# CD_CONTROL_BRD.net
KiCad netlist of a schematic drawn in EAGLE
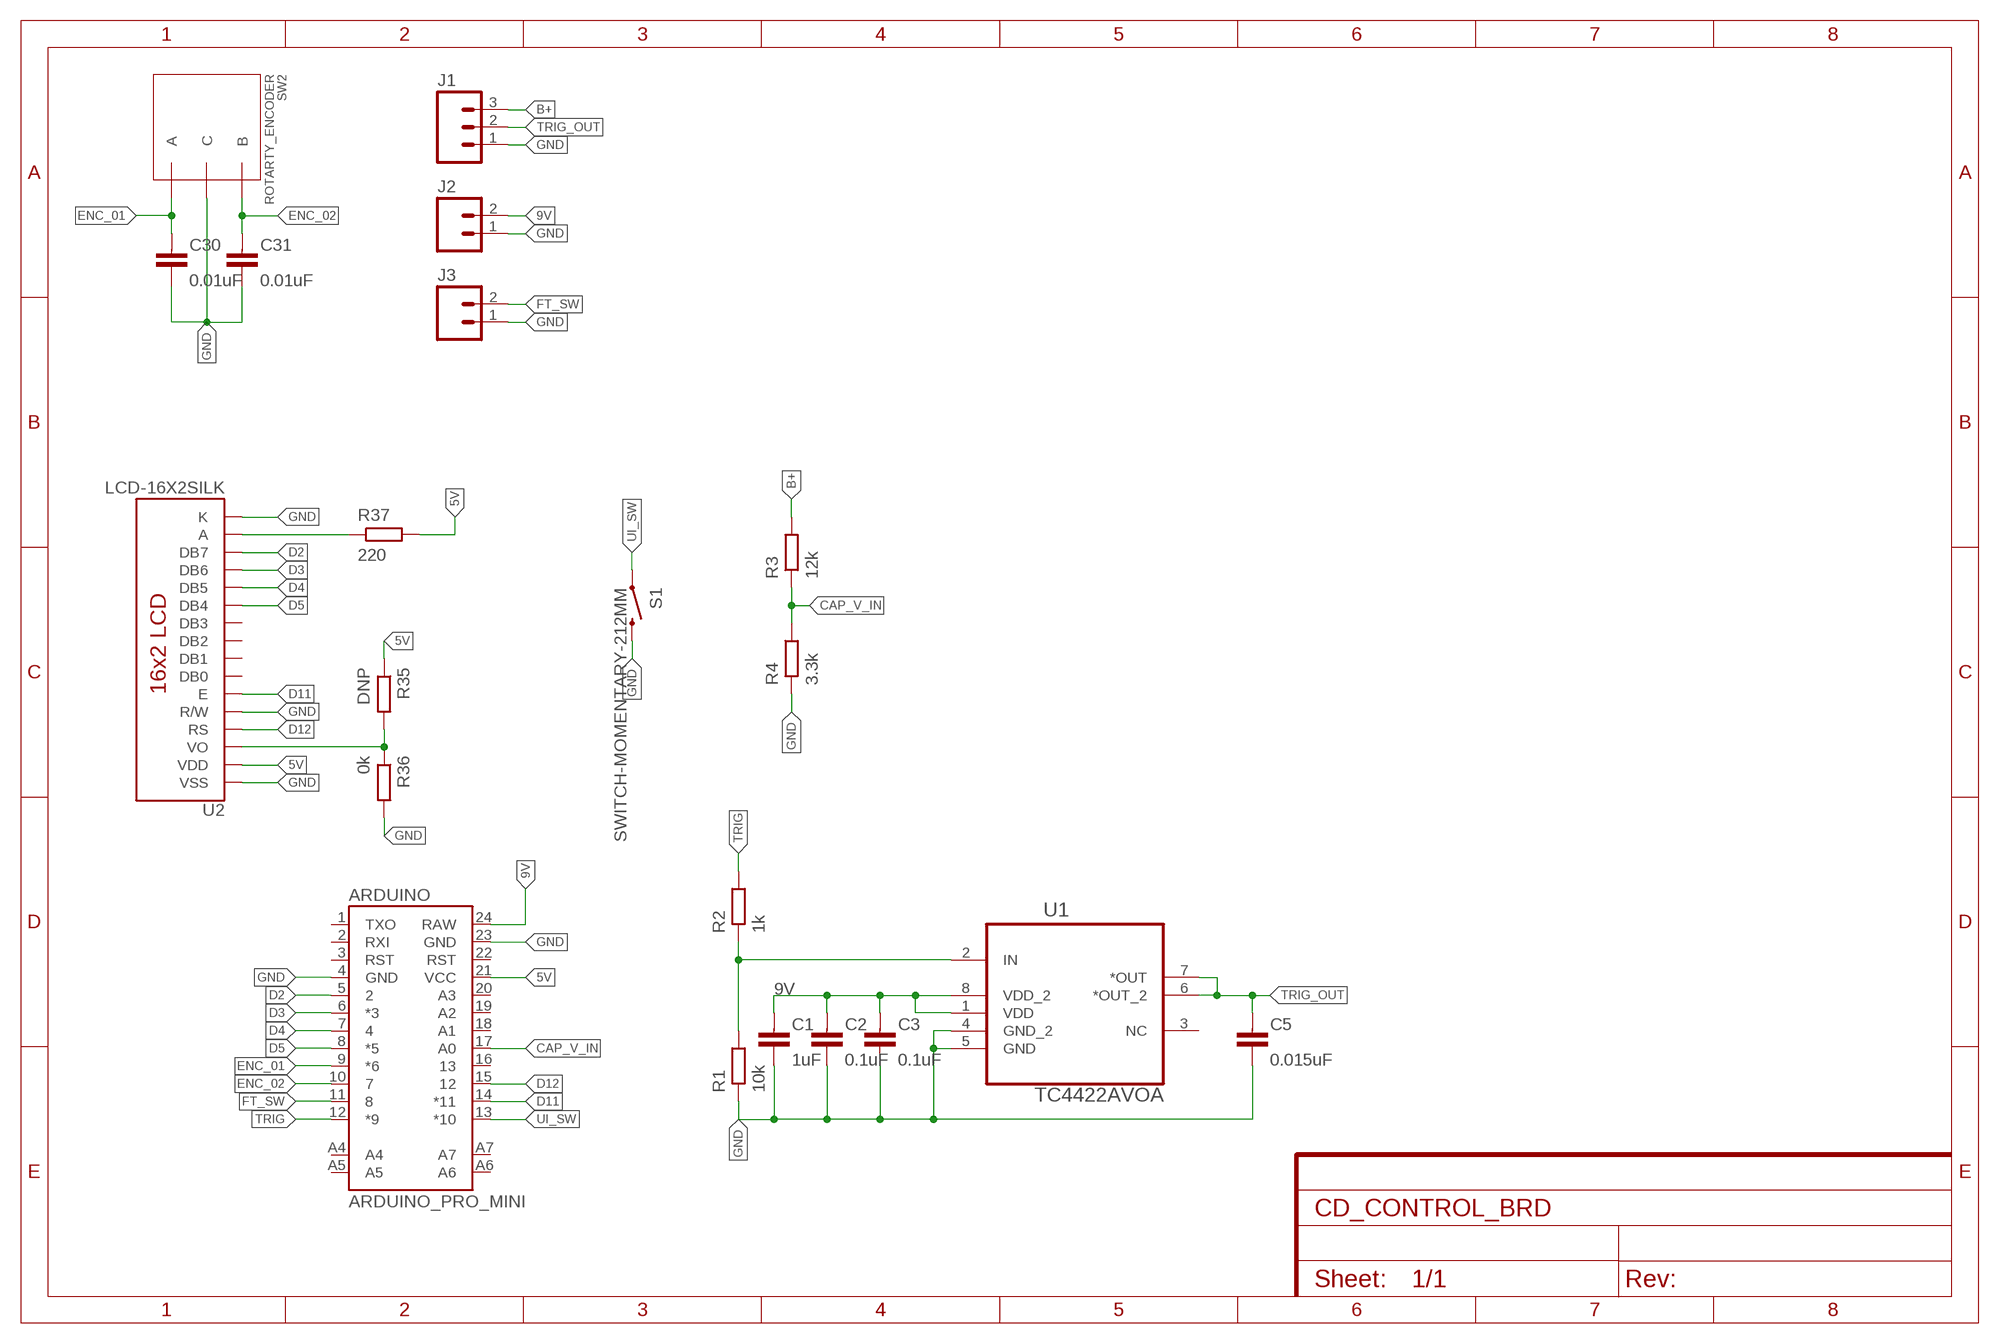
[diagram p0: schematic, sheet 1]

(export (version "E")
  (design (tool "Eeschema 10.0.6"))
  (components
    (comp (ref "ARDUINO")
      (value "ARDUINO_PRO_MINI")
      (footprint "eagle-import:ARDUINO_PRO_MINI")
      (libsource (lib "eagle-import") (part "ARDUINO_PRO_MINI"))
    )
    (comp (ref "C1")
      (value "1uF")
      (footprint "eagle-import:C0805-N")
      (libsource (lib "eagle-import") (part "CAPACITOR0805-N"))
    )
    (comp (ref "C2")
      (value "0.1uF")
      (footprint "eagle-import:C0603-N")
      (libsource (lib "eagle-import") (part "CAPACITOR0603-N"))
    )
    (comp (ref "C3")
      (value "0.1uF")
      (footprint "eagle-import:C0603-N")
      (libsource (lib "eagle-import") (part "CAPACITOR0603-N"))
    )
    (comp (ref "C5")
      (value "0.015uF")
      (footprint "eagle-import:C0603-N")
      (libsource (lib "eagle-import") (part "CAPACITOR0603-N"))
    )
    (comp (ref "C30")
      (value "0.01uF")
      (footprint "eagle-import:C0603-N")
      (libsource (lib "eagle-import") (part "CAPACITOR0603-N"))
    )
    (comp (ref "C31")
      (value "0.01uF")
      (footprint "eagle-import:C0603-N")
      (libsource (lib "eagle-import") (part "CAPACITOR0603-N"))
    )
    (comp (ref "J1")
      (value "M03LOCK_NO_SILK")
      (footprint "eagle-import:1X03_LOCK_NO_SILK")
      (libsource (lib "eagle-import") (part "M03LOCK_NO_SILK"))
    )
    (comp (ref "J2")
      (value "M02LOCK")
      (footprint "eagle-import:1X02_LOCK")
      (libsource (lib "eagle-import") (part "M02LOCK"))
    )
    (comp (ref "J3")
      (value "M02LOCK")
      (footprint "eagle-import:1X02_LOCK")
      (libsource (lib "eagle-import") (part "M02LOCK"))
    )
    (comp (ref "R1")
      (value "10k")
      (footprint "eagle-import:R0603-N")
      (libsource (lib "eagle-import") (part "RESISTOR0603-N"))
    )
    (comp (ref "R2")
      (value "1k")
      (footprint "eagle-import:R0603-N")
      (libsource (lib "eagle-import") (part "RESISTOR0603-N"))
    )
    (comp (ref "R3")
      (value "12k")
      (footprint "eagle-import:R0603-N")
      (libsource (lib "eagle-import") (part "RESISTOR0603-N"))
    )
    (comp (ref "R4")
      (value "3.3k")
      (footprint "eagle-import:R0603-N")
      (libsource (lib "eagle-import") (part "RESISTOR0603-N"))
    )
    (comp (ref "R35")
      (value "DNP")
      (footprint "eagle-import:R0603-N")
      (libsource (lib "eagle-import") (part "RESISTOR0603-N"))
    )
    (comp (ref "R36")
      (value "0k")
      (footprint "eagle-import:R0603-N")
      (libsource (lib "eagle-import") (part "RESISTOR0603-N"))
    )
    (comp (ref "R37")
      (value "220")
      (footprint "eagle-import:R0603-N")
      (libsource (lib "eagle-import") (part "RESISTOR0603-N"))
    )
    (comp (ref "S1")
      (value "SWITCH-MOMENTARY-212MM")
      (footprint "eagle-import:TACTILE-PTH-12MM")
      (libsource (lib "eagle-import") (part "SWITCH-MOMENTARY-212MM"))
    )
    (comp (ref "SW2")
      (value "ROTARTY_ENCODER")
      (footprint "eagle-import:ROTARY_ENC_PLAIN")
      (libsource (lib "eagle-import") (part "ROTARTY_ENCODER"))
    )
    (comp (ref "U1")
      (value "TC4422AVOA")
      (footprint "eagle-import:SOIC127P600X175-8N")
      (libsource (lib "eagle-import") (part "TC4422AVOA"))
    )
    (comp (ref "U2")
      (value "LCD-16X2SILK")
      (footprint "eagle-import:LCD-16X2")
      (libsource (lib "eagle-import") (part "LCD-16X2SILK"))
    )
  )
  (nets
    (net (code "1") (name "5V") (class "Default")
      (node (ref "ARDUINO") (pin "21") (pinfunction "VCC_21") (pintype "bidirectional"))
      (node (ref "R35") (pin "1") (pinfunction "P$1_1") (pintype "passive"))
      (node (ref "R37") (pin "2") (pinfunction "P$2_2") (pintype "passive"))
      (node (ref "U2") (pin "2") (pinfunction "VDD_2") (pintype "power_in"))
    )
    (net (code "2") (name "9V") (class "Default")
      (node (ref "ARDUINO") (pin "24") (pinfunction "RAW_24") (pintype "bidirectional"))
      (node (ref "C1") (pin "1") (pinfunction "1_1") (pintype "passive"))
      (node (ref "C2") (pin "1") (pinfunction "1_1") (pintype "passive"))
      (node (ref "C3") (pin "1") (pinfunction "1_1") (pintype "passive"))
      (node (ref "J2") (pin "2") (pinfunction "2_2") (pintype "passive"))
      (node (ref "U1") (pin "1") (pinfunction "VDD_1") (pintype "power_in"))
      (node (ref "U1") (pin "8") (pinfunction "VDD_2_8") (pintype "power_in"))
    )
    (net (code "3") (name "B+") (class "Default")
      (node (ref "J1") (pin "3") (pinfunction "3_3") (pintype "passive"))
      (node (ref "R3") (pin "2") (pinfunction "P$2_2") (pintype "passive"))
    )
    (net (code "4") (name "CAP_V_IN") (class "Default")
      (node (ref "ARDUINO") (pin "17") (pinfunction "A0_17") (pintype "bidirectional"))
      (node (ref "R3") (pin "1") (pinfunction "P$1_1") (pintype "passive"))
      (node (ref "R4") (pin "2") (pinfunction "P$2_2") (pintype "passive"))
    )
    (net (code "5") (name "D2") (class "Default")
      (node (ref "ARDUINO") (pin "5") (pinfunction "2_5") (pintype "bidirectional"))
      (node (ref "U2") (pin "14") (pinfunction "DB7_14") (pintype "bidirectional"))
    )
    (net (code "6") (name "D3") (class "Default")
      (node (ref "ARDUINO") (pin "6") (pinfunction "*3_6") (pintype "bidirectional"))
      (node (ref "U2") (pin "13") (pinfunction "DB6_13") (pintype "bidirectional"))
    )
    (net (code "7") (name "D4") (class "Default")
      (node (ref "ARDUINO") (pin "7") (pinfunction "4_7") (pintype "bidirectional"))
      (node (ref "U2") (pin "12") (pinfunction "DB5_12") (pintype "bidirectional"))
    )
    (net (code "8") (name "D5") (class "Default")
      (node (ref "ARDUINO") (pin "8") (pinfunction "*5_8") (pintype "bidirectional"))
      (node (ref "U2") (pin "11") (pinfunction "DB4_11") (pintype "bidirectional"))
    )
    (net (code "9") (name "D11") (class "Default")
      (node (ref "ARDUINO") (pin "14") (pinfunction "*11_14") (pintype "bidirectional"))
      (node (ref "U2") (pin "6") (pinfunction "E_6") (pintype "input"))
    )
    (net (code "10") (name "D12") (class "Default")
      (node (ref "ARDUINO") (pin "15") (pinfunction "12_15") (pintype "bidirectional"))
      (node (ref "U2") (pin "4") (pinfunction "RS_4") (pintype "input"))
    )
    (net (code "11") (name "ENC_01") (class "Default")
      (node (ref "ARDUINO") (pin "9") (pinfunction "*6_9") (pintype "bidirectional"))
      (node (ref "C30") (pin "1") (pinfunction "1_1") (pintype "passive"))
      (node (ref "SW2") (pin "A") (pinfunction "A_A") (pintype "bidirectional"))
    )
    (net (code "12") (name "ENC_02") (class "Default")
      (node (ref "ARDUINO") (pin "10") (pinfunction "7_10") (pintype "bidirectional"))
      (node (ref "C31") (pin "1") (pinfunction "1_1") (pintype "passive"))
      (node (ref "SW2") (pin "B") (pinfunction "B_B") (pintype "bidirectional"))
    )
    (net (code "13") (name "FT_SW") (class "Default")
      (node (ref "ARDUINO") (pin "11") (pinfunction "8_11") (pintype "bidirectional"))
      (node (ref "J3") (pin "2") (pinfunction "2_2") (pintype "passive"))
    )
    (net (code "14") (name "GND") (class "Default")
      (node (ref "ARDUINO") (pin "23") (pinfunction "GND_23") (pintype "bidirectional"))
      (node (ref "ARDUINO") (pin "4") (pinfunction "GND_4") (pintype "bidirectional"))
      (node (ref "C1") (pin "2") (pinfunction "2_2") (pintype "passive"))
      (node (ref "C2") (pin "2") (pinfunction "2_2") (pintype "passive"))
      (node (ref "C3") (pin "2") (pinfunction "2_2") (pintype "passive"))
      (node (ref "C30") (pin "2") (pinfunction "2_2") (pintype "passive"))
      (node (ref "C31") (pin "2") (pinfunction "2_2") (pintype "passive"))
      (node (ref "C5") (pin "2") (pinfunction "2_2") (pintype "passive"))
      (node (ref "J1") (pin "1") (pinfunction "1_1") (pintype "passive"))
      (node (ref "J2") (pin "1") (pinfunction "1_1") (pintype "passive"))
      (node (ref "J3") (pin "1") (pinfunction "1_1") (pintype "passive"))
      (node (ref "R1") (pin "1") (pinfunction "P$1_1") (pintype "passive"))
      (node (ref "R36") (pin "2") (pinfunction "P$2_2") (pintype "passive"))
      (node (ref "R4") (pin "1") (pinfunction "P$1_1") (pintype "passive"))
      (node (ref "S1") (pin "3") (pinfunction "2_3") (pintype "passive"))
      (node (ref "SW2") (pin "C") (pinfunction "C_C") (pintype "bidirectional"))
      (node (ref "U1") (pin "4") (pinfunction "GND_2_4") (pintype "passive"))
      (node (ref "U1") (pin "5") (pinfunction "GND_5") (pintype "passive"))
      (node (ref "U2") (pin "1") (pinfunction "VSS_1") (pintype "power_in"))
      (node (ref "U2") (pin "16") (pinfunction "K_16") (pintype "power_in"))
      (node (ref "U2") (pin "5") (pinfunction "R/W_5") (pintype "input"))
    )
    (net (code "15") (name "Net-(R1-P$2)") (class "Default")
      (node (ref "R1") (pin "2") (pinfunction "P$2_2") (pintype "passive"))
      (node (ref "R2") (pin "1") (pinfunction "P$1_1") (pintype "passive"))
      (node (ref "U1") (pin "2") (pinfunction "IN_2") (pintype "input"))
    )
    (net (code "16") (name "Net-(R35-P$2)") (class "Default")
      (node (ref "R35") (pin "2") (pinfunction "P$2_2") (pintype "passive"))
      (node (ref "R36") (pin "1") (pinfunction "P$1_1") (pintype "passive"))
      (node (ref "U2") (pin "3") (pinfunction "VO_3") (pintype "bidirectional"))
    )
    (net (code "17") (name "Net-(R37-P$1)") (class "Default")
      (node (ref "R37") (pin "1") (pinfunction "P$1_1") (pintype "passive"))
      (node (ref "U2") (pin "15") (pinfunction "A_15") (pintype "power_in"))
    )
    (net (code "18") (name "TRIG") (class "Default")
      (node (ref "ARDUINO") (pin "12") (pinfunction "*9_12") (pintype "bidirectional"))
      (node (ref "R2") (pin "2") (pinfunction "P$2_2") (pintype "passive"))
    )
    (net (code "19") (name "TRIG_OUT") (class "Default")
      (node (ref "C5") (pin "1") (pinfunction "1_1") (pintype "passive"))
      (node (ref "J1") (pin "2") (pinfunction "2_2") (pintype "passive"))
      (node (ref "U1") (pin "6") (pinfunction "*OUT_2_6") (pintype "output"))
      (node (ref "U1") (pin "7") (pinfunction "*OUT_7") (pintype "output"))
    )
    (net (code "20") (name "UI_SW") (class "Default")
      (node (ref "ARDUINO") (pin "13") (pinfunction "*10_13") (pintype "bidirectional"))
      (node (ref "S1") (pin "1") (pinfunction "1_1") (pintype "passive"))
    )
    (net (code "21") (name "unconnected-(ARDUINO-13-Pad16)") (class "Default")
      (node (ref "ARDUINO") (pin "16") (pinfunction "13_16") (pintype "bidirectional"))
    )
    (net (code "22") (name "unconnected-(ARDUINO-A1-Pad18)") (class "Default")
      (node (ref "ARDUINO") (pin "18") (pinfunction "A1_18") (pintype "bidirectional"))
    )
    (net (code "23") (name "unconnected-(ARDUINO-A2-Pad19)") (class "Default")
      (node (ref "ARDUINO") (pin "19") (pinfunction "A2_19") (pintype "bidirectional"))
    )
    (net (code "24") (name "unconnected-(ARDUINO-A3-Pad20)") (class "Default")
      (node (ref "ARDUINO") (pin "20") (pinfunction "A3_20") (pintype "bidirectional"))
    )
    (net (code "25") (name "unconnected-(ARDUINO-PadA4)") (class "Default")
      (node (ref "ARDUINO") (pin "A4") (pinfunction "A4_A4") (pintype "bidirectional"))
    )
    (net (code "26") (name "unconnected-(ARDUINO-PadA5)") (class "Default")
      (node (ref "ARDUINO") (pin "A5") (pinfunction "A5_A5") (pintype "bidirectional"))
    )
    (net (code "27") (name "unconnected-(ARDUINO-PadA6)") (class "Default")
      (node (ref "ARDUINO") (pin "A6") (pinfunction "A6_A6") (pintype "bidirectional"))
    )
    (net (code "28") (name "unconnected-(ARDUINO-PadA7)") (class "Default")
      (node (ref "ARDUINO") (pin "A7") (pinfunction "A7_A7") (pintype "bidirectional"))
    )
    (net (code "29") (name "unconnected-(ARDUINO-RST-Pad3)") (class "Default")
      (node (ref "ARDUINO") (pin "3") (pinfunction "RST_3") (pintype "bidirectional"))
    )
    (net (code "30") (name "unconnected-(ARDUINO-RST-Pad22)") (class "Default")
      (node (ref "ARDUINO") (pin "22") (pinfunction "RST_22") (pintype "bidirectional"))
    )
    (net (code "31") (name "unconnected-(ARDUINO-RXI-Pad2)") (class "Default")
      (node (ref "ARDUINO") (pin "2") (pinfunction "RXI_2") (pintype "bidirectional"))
    )
    (net (code "32") (name "unconnected-(ARDUINO-TXO-Pad1)") (class "Default")
      (node (ref "ARDUINO") (pin "1") (pinfunction "TXO_1") (pintype "bidirectional"))
    )
    (net (code "33") (name "unconnected-(U1-NC-Pad3)") (class "Default")
      (node (ref "U1") (pin "3") (pinfunction "NC_3") (pintype "no_connect"))
    )
    (net (code "34") (name "unconnected-(U2-DB0-Pad7)") (class "Default")
      (node (ref "U2") (pin "7") (pinfunction "DB0_7") (pintype "bidirectional"))
    )
    (net (code "35") (name "unconnected-(U2-DB1-Pad8)") (class "Default")
      (node (ref "U2") (pin "8") (pinfunction "DB1_8") (pintype "bidirectional"))
    )
    (net (code "36") (name "unconnected-(U2-DB2-Pad9)") (class "Default")
      (node (ref "U2") (pin "9") (pinfunction "DB2_9") (pintype "bidirectional"))
    )
    (net (code "37") (name "unconnected-(U2-DB3-Pad10)") (class "Default")
      (node (ref "U2") (pin "10") (pinfunction "DB3_10") (pintype "bidirectional"))
    )
  )
)
